# ocmod_module_playground_smt_v1.net
KiCad netlist of a schematic drawn in EAGLE
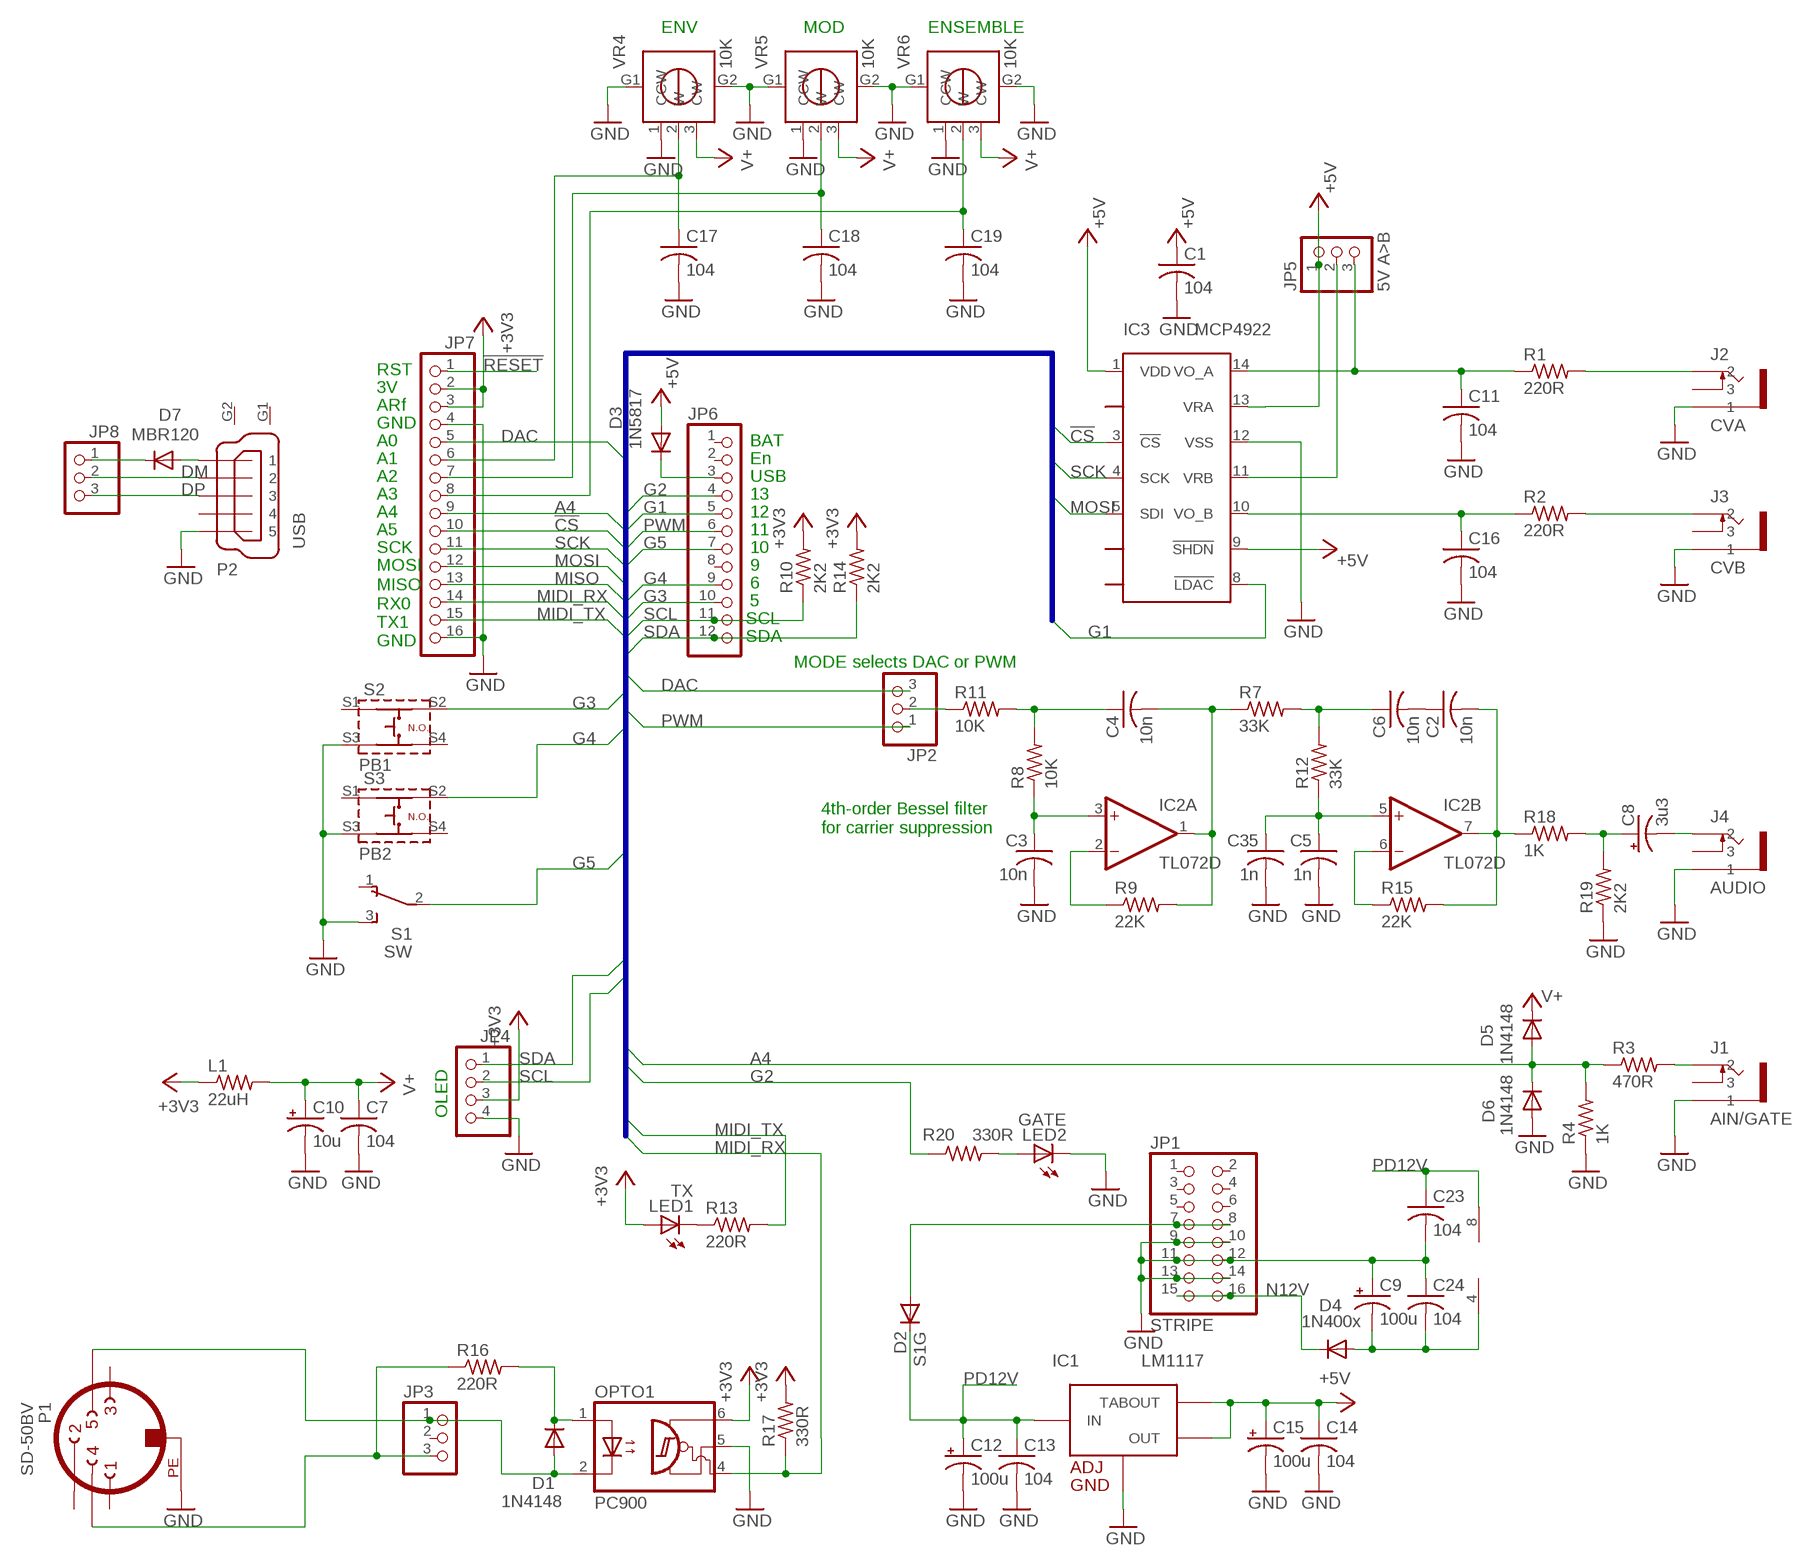
[diagram p0: schematic, sheet 1]

(export (version "E")
  (design (tool "Eeschema 10.0.6"))
  (components
    (comp (ref "C1")
      (value "104")
      (footprint "eagle-import:C0805K")
      (libsource (lib "eagle-import") (part "C-USC0805K"))
    )
    (comp (ref "C2")
      (value "10n")
      (footprint "eagle-import:C0805K")
      (libsource (lib "eagle-import") (part "C-USC0805K"))
    )
    (comp (ref "C3")
      (value "10n")
      (footprint "eagle-import:C0805K")
      (libsource (lib "eagle-import") (part "C-USC0805K"))
    )
    (comp (ref "C4")
      (value "10n")
      (footprint "eagle-import:C0805K")
      (libsource (lib "eagle-import") (part "C-USC0805K"))
    )
    (comp (ref "C5")
      (value "1n")
      (footprint "eagle-import:C0805K")
      (libsource (lib "eagle-import") (part "C-USC0805K"))
    )
    (comp (ref "C6")
      (value "10n")
      (footprint "eagle-import:C0805K")
      (libsource (lib "eagle-import") (part "C-USC0805K"))
    )
    (comp (ref "C7")
      (value "104")
      (footprint "eagle-import:C0805K")
      (libsource (lib "eagle-import") (part "C-USC0805K"))
    )
    (comp (ref "C8")
      (value "3u3")
      (footprint "eagle-import:B_3528-21R")
      (libsource (lib "eagle-import") (part "CPOL-USB/3528-21R"))
    )
    (comp (ref "C9")
      (value "100u")
      (footprint "eagle-import:B_3528-21R")
      (libsource (lib "eagle-import") (part "CPOL-USB/3528-21R"))
    )
    (comp (ref "C10")
      (value "10u")
      (footprint "eagle-import:B_3528-21R")
      (libsource (lib "eagle-import") (part "CPOL-USB/3528-21R"))
    )
    (comp (ref "C11")
      (value "104")
      (footprint "eagle-import:C0805K")
      (libsource (lib "eagle-import") (part "C-USC0805K"))
    )
    (comp (ref "C12")
      (value "100u")
      (footprint "eagle-import:B_3528-21R")
      (libsource (lib "eagle-import") (part "CPOL-USB/3528-21R"))
    )
    (comp (ref "C13")
      (value "104")
      (footprint "eagle-import:C0805K")
      (libsource (lib "eagle-import") (part "C-USC0805K"))
    )
    (comp (ref "C14")
      (value "104")
      (footprint "eagle-import:C0805K")
      (libsource (lib "eagle-import") (part "C-USC0805K"))
    )
    (comp (ref "C15")
      (value "100u")
      (footprint "eagle-import:B_3528-21R")
      (libsource (lib "eagle-import") (part "CPOL-USB/3528-21R"))
    )
    (comp (ref "C16")
      (value "104")
      (footprint "eagle-import:C0805K")
      (libsource (lib "eagle-import") (part "C-USC0805K"))
    )
    (comp (ref "C17")
      (value "104")
      (footprint "eagle-import:C0805K")
      (libsource (lib "eagle-import") (part "C-USC0805K"))
    )
    (comp (ref "C18")
      (value "104")
      (footprint "eagle-import:C0805K")
      (libsource (lib "eagle-import") (part "C-USC0805K"))
    )
    (comp (ref "C19")
      (value "104")
      (footprint "eagle-import:C0805K")
      (libsource (lib "eagle-import") (part "C-USC0805K"))
    )
    (comp (ref "C23")
      (value "104")
      (footprint "eagle-import:C0805K")
      (libsource (lib "eagle-import") (part "C-USC0805K"))
    )
    (comp (ref "C24")
      (value "104")
      (footprint "eagle-import:C0805K")
      (libsource (lib "eagle-import") (part "C-USC0805K"))
    )
    (comp (ref "C35")
      (value "1n")
      (footprint "eagle-import:C0805K")
      (libsource (lib "eagle-import") (part "C-USC0805K"))
    )
    (comp (ref "D1")
      (value "1N4148")
      (footprint "eagle-import:SOD123")
      (libsource (lib "eagle-import") (part "DIODE-SOD123"))
    )
    (comp (ref "D2")
      (value "S1G")
      (footprint "eagle-import:DO-214AC")
      (libsource (lib "eagle-import") (part "DIODE-DO-214AC"))
    )
    (comp (ref "D3")
      (value "1N5817")
      (footprint "eagle-import:DO214AC")
      (libsource (lib "eagle-import") (part "DIODE-DO214AC"))
    )
    (comp (ref "D4")
      (value "1N400x")
      (footprint "eagle-import:DO-214AC")
      (libsource (lib "eagle-import") (part "DIODE-DO-214AC"))
    )
    (comp (ref "D5")
      (value "1N4148")
      (footprint "eagle-import:SOD123")
      (libsource (lib "eagle-import") (part "DIODE-SOD123"))
    )
    (comp (ref "D6")
      (value "1N4148")
      (footprint "eagle-import:SOD123")
      (libsource (lib "eagle-import") (part "DIODE-SOD123"))
    )
    (comp (ref "D7")
      (value "MBR120")
      (footprint "eagle-import:SOD123")
      (libsource (lib "eagle-import") (part "DIODE-SOD123"))
    )
    (comp (ref "IC1")
      (value "LM1117")
      (footprint "eagle-import:SOT223")
      (libsource (lib "eagle-import") (part "LM1117"))
    )
    (comp (ref "IC2")
      (value "TL072D")
      (footprint "eagle-import:SO08")
      (libsource (lib "eagle-import") (part "TL072D"))
    )
    (comp (ref "IC3")
      (value "MCP4922")
      (footprint "eagle-import:SO14")
      (libsource (lib "eagle-import") (part "MCP4922D"))
    )
    (comp (ref "J1")
      (value "AIN/GATE")
      (footprint "eagle-import:WQP-PJ301M-12_JACK")
      (libsource (lib "eagle-import") (part "WQP-PJ301M-12_JACK"))
    )
    (comp (ref "J2")
      (value "CVA")
      (footprint "eagle-import:WQP-PJ301M-12_JACK")
      (libsource (lib "eagle-import") (part "WQP-PJ301M-12_JACK"))
    )
    (comp (ref "J3")
      (value "CVB")
      (footprint "eagle-import:WQP-PJ301M-12_JACK")
      (libsource (lib "eagle-import") (part "WQP-PJ301M-12_JACK"))
    )
    (comp (ref "J4")
      (value "AUDIO")
      (footprint "eagle-import:WQP-PJ301M-12_JACK")
      (libsource (lib "eagle-import") (part "WQP-PJ301M-12_JACK"))
    )
    (comp (ref "JP1")
      (value "STRIPE")
      (footprint "eagle-import:2X08")
      (libsource (lib "eagle-import") (part "PINHD-2X8"))
    )
    (comp (ref "JP2")
      (value "PINHD-1X3")
      (footprint "eagle-import:1X03")
      (libsource (lib "eagle-import") (part "PINHD-1X3"))
    )
    (comp (ref "JP3")
      (value "PINHD-1X3")
      (footprint "eagle-import:1X03")
      (libsource (lib "eagle-import") (part "pinhead_PINHD-1X3"))
    )
    (comp (ref "JP4")
      (value "PINHD-1X4")
      (footprint "eagle-import:1X04")
      (libsource (lib "eagle-import") (part "PINHD-1X4"))
    )
    (comp (ref "JP5")
      (value "5V A>B")
      (footprint "eagle-import:1X03")
      (libsource (lib "eagle-import") (part "PINHD-1X3"))
    )
    (comp (ref "JP6")
      (value "PINHD-1X12")
      (footprint "eagle-import:1X12")
      (libsource (lib "eagle-import") (part "PINHD-1X12"))
    )
    (comp (ref "JP7")
      (value "PINHD-1X16")
      (footprint "eagle-import:1X16")
      (libsource (lib "eagle-import") (part "PINHD-1X16"))
    )
    (comp (ref "JP8")
      (value "PINHD-1X3")
      (footprint "eagle-import:1X03")
      (libsource (lib "eagle-import") (part "PINHD-1X3"))
    )
    (comp (ref "L1")
      (value "22uH")
      (footprint "eagle-import:R0805")
      (libsource (lib "eagle-import") (part "R-US_R0805"))
    )
    (comp (ref "LED1")
      (value "TX")
      (footprint "eagle-import:LED3MM")
      (libsource (lib "eagle-import") (part "LED3MM"))
    )
    (comp (ref "LED2")
      (value "GATE")
      (footprint "eagle-import:LED3MM")
      (libsource (lib "eagle-import") (part "LED3MM"))
    )
    (comp (ref "OPTO1")
      (value "PC900")
      (footprint "eagle-import:DIL06N")
      (libsource (lib "eagle-import") (part "H11L1-MN"))
    )
    (comp (ref "P1")
      (value "SD-50BV")
      (footprint "eagle-import:SD-50BV_P")
      (libsource (lib "eagle-import") (part "SD-50BV"))
    )
    (comp (ref "P2")
      (value "USB")
      (footprint "eagle-import:MINI_USB5_WURTH")
      (libsource (lib "eagle-import") (part "MINI_USB5_WURTH"))
    )
    (comp (ref "R1")
      (value "220R")
      (footprint "eagle-import:R0805")
      (libsource (lib "eagle-import") (part "R-US_R0805"))
    )
    (comp (ref "R2")
      (value "220R")
      (footprint "eagle-import:R0805")
      (libsource (lib "eagle-import") (part "R-US_R0805"))
    )
    (comp (ref "R3")
      (value "470R")
      (footprint "eagle-import:R0805")
      (libsource (lib "eagle-import") (part "R-US_R0805"))
    )
    (comp (ref "R4")
      (value "1K")
      (footprint "eagle-import:R0805")
      (libsource (lib "eagle-import") (part "R-US_R0805"))
    )
    (comp (ref "R7")
      (value "33K")
      (footprint "eagle-import:R0805")
      (libsource (lib "eagle-import") (part "R-US_R0805"))
    )
    (comp (ref "R8")
      (value "10K")
      (footprint "eagle-import:R0805")
      (libsource (lib "eagle-import") (part "R-US_R0805"))
    )
    (comp (ref "R9")
      (value "22K")
      (footprint "eagle-import:R0805")
      (libsource (lib "eagle-import") (part "R-US_R0805"))
    )
    (comp (ref "R10")
      (value "2K2")
      (footprint "eagle-import:R0805")
      (libsource (lib "eagle-import") (part "R-US_R0805"))
    )
    (comp (ref "R11")
      (value "10K")
      (footprint "eagle-import:R0805")
      (libsource (lib "eagle-import") (part "R-US_R0805"))
    )
    (comp (ref "R12")
      (value "33K")
      (footprint "eagle-import:R0805")
      (libsource (lib "eagle-import") (part "R-US_R0805"))
    )
    (comp (ref "R13")
      (value "220R")
      (footprint "eagle-import:R0805")
      (libsource (lib "eagle-import") (part "R-US_R0805"))
    )
    (comp (ref "R14")
      (value "2K2")
      (footprint "eagle-import:R0805")
      (libsource (lib "eagle-import") (part "R-US_R0805"))
    )
    (comp (ref "R15")
      (value "22K")
      (footprint "eagle-import:R0805")
      (libsource (lib "eagle-import") (part "R-US_R0805"))
    )
    (comp (ref "R16")
      (value "220R")
      (footprint "eagle-import:R0805")
      (libsource (lib "eagle-import") (part "R-US_R0805"))
    )
    (comp (ref "R17")
      (value "330R")
      (footprint "eagle-import:R0805")
      (libsource (lib "eagle-import") (part "R-US_R0805"))
    )
    (comp (ref "R18")
      (value "1K")
      (footprint "eagle-import:R0805")
      (libsource (lib "eagle-import") (part "R-US_R0805"))
    )
    (comp (ref "R19")
      (value "2K2")
      (footprint "eagle-import:R0805")
      (libsource (lib "eagle-import") (part "R-US_R0805"))
    )
    (comp (ref "R20")
      (value "330R")
      (footprint "eagle-import:R0805")
      (libsource (lib "eagle-import") (part "R-US_R0805"))
    )
    (comp (ref "S1")
      (value "SW")
      (footprint "eagle-import:TL3XPO")
      (libsource (lib "eagle-import") (part "TL36PO"))
    )
    (comp (ref "S2")
      (value "PB1")
      (footprint "eagle-import:TACTSW_6MM_P")
      (libsource (lib "eagle-import") (part "TACTSW_6MM"))
    )
    (comp (ref "S3")
      (value "PB2")
      (footprint "eagle-import:TACTSW_6MM_P")
      (libsource (lib "eagle-import") (part "TACTSW_6MM"))
    )
    (comp (ref "VR4")
      (value "10K")
      (footprint "eagle-import:ALPHA_9MM_VERT_P")
      (libsource (lib "eagle-import") (part "ALPHA_9MM_VERT"))
    )
    (comp (ref "VR5")
      (value "10K")
      (footprint "eagle-import:ALPHA_9MM_VERT_P")
      (libsource (lib "eagle-import") (part "ALPHA_9MM_VERT"))
    )
    (comp (ref "VR6")
      (value "10K")
      (footprint "eagle-import:ALPHA_9MM_VERT_P")
      (libsource (lib "eagle-import") (part "ALPHA_9MM_VERT"))
    )
  )
  (nets
    (net (code "1") (name "+3V3") (class "Default")
      (node (ref "JP4") (pin "3") (pinfunction "3_3") (pintype "passive"))
      (node (ref "JP7") (pin "2") (pinfunction "2_2") (pintype "passive"))
      (node (ref "JP7") (pin "3") (pinfunction "3_3") (pintype "passive"))
      (node (ref "L1") (pin "1") (pinfunction "1_1") (pintype "passive"))
      (node (ref "LED1") (pin "A") (pinfunction "A_A") (pintype "passive"))
      (node (ref "OPTO1") (pin "6") (pinfunction "VCC_6") (pintype "passive"))
      (node (ref "R10") (pin "2") (pinfunction "2_2") (pintype "passive"))
      (node (ref "R14") (pin "2") (pinfunction "2_2") (pintype "passive"))
      (node (ref "R17") (pin "2") (pinfunction "2_2") (pintype "passive"))
    )
    (net (code "2") (name "+5V") (class "Default")
      (node (ref "C1") (pin "1") (pinfunction "1_1") (pintype "passive"))
      (node (ref "C14") (pin "1") (pinfunction "1_1") (pintype "passive"))
      (node (ref "C15") (pin "+") (pinfunction "+_+") (pintype "passive"))
      (node (ref "D3") (pin "A") (pinfunction "A_A") (pintype "passive"))
      (node (ref "IC1") (pin "1") (pinfunction "TABOUT_1") (pintype "passive"))
      (node (ref "IC1") (pin "4") (pinfunction "OUT_4") (pintype "passive"))
      (node (ref "IC3") (pin "1") (pinfunction "VDD_1") (pintype "bidirectional"))
      (node (ref "IC3") (pin "13") (pinfunction "VRA_13") (pintype "bidirectional"))
      (node (ref "IC3") (pin "9") (pinfunction "~{SHDN}_9") (pintype "bidirectional"))
      (node (ref "JP5") (pin "1") (pinfunction "1_1") (pintype "passive"))
    )
    (net (code "3") (name "/A4") (class "Default")
      (node (ref "D5") (pin "A") (pinfunction "A_A") (pintype "passive"))
      (node (ref "D6") (pin "C") (pinfunction "C_C") (pintype "passive"))
      (node (ref "JP7") (pin "9") (pinfunction "9_9") (pintype "passive"))
      (node (ref "R3") (pin "1") (pinfunction "1_1") (pintype "passive"))
      (node (ref "R4") (pin "2") (pinfunction "2_2") (pintype "passive"))
    )
    (net (code "4") (name "/DAC") (class "Default")
      (node (ref "JP2") (pin "3") (pinfunction "3_3") (pintype "passive"))
      (node (ref "JP7") (pin "5") (pinfunction "5_5") (pintype "passive"))
    )
    (net (code "5") (name "/DM") (class "Default")
      (node (ref "JP8") (pin "2") (pinfunction "2_2") (pintype "passive"))
      (node (ref "P2") (pin "2") (pinfunction "2_2") (pintype "passive"))
    )
    (net (code "6") (name "/DP") (class "Default")
      (node (ref "JP8") (pin "3") (pinfunction "3_3") (pintype "passive"))
      (node (ref "P2") (pin "3") (pinfunction "3_3") (pintype "passive"))
    )
    (net (code "7") (name "/G1") (class "Default")
      (node (ref "IC3") (pin "8") (pinfunction "~{LDAC}_8") (pintype "bidirectional"))
      (node (ref "JP6") (pin "5") (pinfunction "5_5") (pintype "passive"))
    )
    (net (code "8") (name "/G2") (class "Default")
      (node (ref "JP6") (pin "4") (pinfunction "4_4") (pintype "passive"))
      (node (ref "R20") (pin "1") (pinfunction "1_1") (pintype "passive"))
    )
    (net (code "9") (name "/G3") (class "Default")
      (node (ref "JP6") (pin "10") (pinfunction "10_10") (pintype "passive"))
      (node (ref "S2") (pin "S2") (pinfunction "2_S2") (pintype "passive"))
    )
    (net (code "10") (name "/G4") (class "Default")
      (node (ref "JP6") (pin "9") (pinfunction "9_9") (pintype "passive"))
      (node (ref "S3") (pin "S2") (pinfunction "2_S2") (pintype "passive"))
    )
    (net (code "11") (name "/G5") (class "Default")
      (node (ref "JP6") (pin "7") (pinfunction "7_7") (pintype "passive"))
      (node (ref "S1") (pin "2") (pinfunction "P_2") (pintype "passive"))
    )
    (net (code "12") (name "/MIDI_RX") (class "Default")
      (node (ref "JP7") (pin "14") (pinfunction "14_14") (pintype "passive"))
      (node (ref "OPTO1") (pin "4") (pinfunction "VO_4") (pintype "passive"))
      (node (ref "R17") (pin "1") (pinfunction "1_1") (pintype "passive"))
    )
    (net (code "13") (name "/MIDI_TX") (class "Default")
      (node (ref "JP7") (pin "15") (pinfunction "15_15") (pintype "passive"))
      (node (ref "R13") (pin "2") (pinfunction "2_2") (pintype "passive"))
    )
    (net (code "14") (name "/MISO") (class "Default")
      (node (ref "JP7") (pin "13") (pinfunction "13_13") (pintype "passive"))
    )
    (net (code "15") (name "/MOSI") (class "Default")
      (node (ref "IC3") (pin "5") (pinfunction "SDI_5") (pintype "bidirectional"))
      (node (ref "JP7") (pin "12") (pinfunction "12_12") (pintype "passive"))
    )
    (net (code "16") (name "/N12V") (class "Default")
      (node (ref "D4") (pin "C") (pinfunction "C_C") (pintype "passive"))
      (node (ref "JP1") (pin "15") (pinfunction "15_15") (pintype "passive"))
      (node (ref "JP1") (pin "16") (pinfunction "16_16") (pintype "passive"))
    )
    (net (code "17") (name "/PD12V") (class "Default")
      (node (ref "C12") (pin "+") (pinfunction "+_+") (pintype "passive"))
      (node (ref "C13") (pin "1") (pinfunction "1_1") (pintype "passive"))
      (node (ref "C23") (pin "1") (pinfunction "1_1") (pintype "passive"))
      (node (ref "D2") (pin "C") (pinfunction "C_C") (pintype "passive"))
      (node (ref "IC1") (pin "3") (pinfunction "IN_3") (pintype "passive"))
      (node (ref "IC2") (pin "8") (pinfunction "V+_8") (pintype "power_in"))
    )
    (net (code "18") (name "/PWM") (class "Default")
      (node (ref "JP2") (pin "1") (pinfunction "1_1") (pintype "passive"))
      (node (ref "JP6") (pin "6") (pinfunction "6_6") (pintype "passive"))
    )
    (net (code "19") (name "/SCK") (class "Default")
      (node (ref "IC3") (pin "4") (pinfunction "SCK_4") (pintype "bidirectional"))
      (node (ref "JP7") (pin "11") (pinfunction "11_11") (pintype "passive"))
    )
    (net (code "20") (name "/SCL") (class "Default")
      (node (ref "JP4") (pin "2") (pinfunction "2_2") (pintype "passive"))
      (node (ref "JP6") (pin "11") (pinfunction "11_11") (pintype "passive"))
      (node (ref "R10") (pin "1") (pinfunction "1_1") (pintype "passive"))
    )
    (net (code "21") (name "/SDA") (class "Default")
      (node (ref "JP4") (pin "1") (pinfunction "1_1") (pintype "passive"))
      (node (ref "JP6") (pin "12") (pinfunction "12_12") (pintype "passive"))
      (node (ref "R14") (pin "1") (pinfunction "1_1") (pintype "passive"))
    )
    (net (code "22") (name "/~{CS}") (class "Default")
      (node (ref "IC3") (pin "3") (pinfunction "~{CS}_3") (pintype "bidirectional"))
      (node (ref "JP7") (pin "10") (pinfunction "10_10") (pintype "passive"))
    )
    (net (code "23") (name "/~{RESET}") (class "Default")
      (node (ref "JP7") (pin "1") (pinfunction "1_1") (pintype "passive"))
    )
    (net (code "24") (name "GND") (class "Default")
      (node (ref "C1") (pin "2") (pinfunction "2_2") (pintype "passive"))
      (node (ref "C10") (pin "-") (pinfunction "-_-") (pintype "passive"))
      (node (ref "C11") (pin "2") (pinfunction "2_2") (pintype "passive"))
      (node (ref "C12") (pin "-") (pinfunction "-_-") (pintype "passive"))
      (node (ref "C13") (pin "2") (pinfunction "2_2") (pintype "passive"))
      (node (ref "C14") (pin "2") (pinfunction "2_2") (pintype "passive"))
      (node (ref "C15") (pin "-") (pinfunction "-_-") (pintype "passive"))
      (node (ref "C16") (pin "2") (pinfunction "2_2") (pintype "passive"))
      (node (ref "C17") (pin "2") (pinfunction "2_2") (pintype "passive"))
      (node (ref "C18") (pin "2") (pinfunction "2_2") (pintype "passive"))
      (node (ref "C19") (pin "2") (pinfunction "2_2") (pintype "passive"))
      (node (ref "C23") (pin "2") (pinfunction "2_2") (pintype "passive"))
      (node (ref "C24") (pin "1") (pinfunction "1_1") (pintype "passive"))
      (node (ref "C3") (pin "2") (pinfunction "2_2") (pintype "passive"))
      (node (ref "C35") (pin "2") (pinfunction "2_2") (pintype "passive"))
      (node (ref "C5") (pin "2") (pinfunction "2_2") (pintype "passive"))
      (node (ref "C7") (pin "2") (pinfunction "2_2") (pintype "passive"))
      (node (ref "C9") (pin "+") (pinfunction "+_+") (pintype "passive"))
      (node (ref "D6") (pin "A") (pinfunction "A_A") (pintype "passive"))
      (node (ref "IC1") (pin "2") (pinfunction "ADJ/GND_2") (pintype "passive"))
      (node (ref "IC3") (pin "12") (pinfunction "VSS_12") (pintype "bidirectional"))
      (node (ref "J1") (pin "P$3") (pinfunction "1_P$3") (pintype "passive"))
      (node (ref "J2") (pin "P$3") (pinfunction "1_P$3") (pintype "passive"))
      (node (ref "J3") (pin "P$3") (pinfunction "1_P$3") (pintype "passive"))
      (node (ref "J4") (pin "P$3") (pinfunction "1_P$3") (pintype "passive"))
      (node (ref "JP1") (pin "10") (pinfunction "10_10") (pintype "passive"))
      (node (ref "JP1") (pin "11") (pinfunction "11_11") (pintype "passive"))
      (node (ref "JP1") (pin "12") (pinfunction "12_12") (pintype "passive"))
      (node (ref "JP1") (pin "13") (pinfunction "13_13") (pintype "passive"))
      (node (ref "JP1") (pin "14") (pinfunction "14_14") (pintype "passive"))
      (node (ref "JP1") (pin "9") (pinfunction "9_9") (pintype "passive"))
      (node (ref "JP4") (pin "4") (pinfunction "4_4") (pintype "passive"))
      (node (ref "JP7") (pin "16") (pinfunction "16_16") (pintype "passive"))
      (node (ref "JP7") (pin "4") (pinfunction "4_4") (pintype "passive"))
      (node (ref "LED2") (pin "K") (pinfunction "C_K") (pintype "passive"))
      (node (ref "OPTO1") (pin "5") (pinfunction "GND_5") (pintype "passive"))
      (node (ref "P1") (pin "PE") (pinfunction "PE_PE") (pintype "power_in"))
      (node (ref "P2") (pin "5") (pinfunction "5_5") (pintype "passive"))
      (node (ref "R19") (pin "1") (pinfunction "1_1") (pintype "passive"))
      (node (ref "R4") (pin "1") (pinfunction "1_1") (pintype "passive"))
      (node (ref "S1") (pin "3") (pinfunction "S_3") (pintype "passive"))
      (node (ref "S2") (pin "S3") (pinfunction "3_S3") (pintype "passive"))
      (node (ref "S3") (pin "S3") (pinfunction "3_S3") (pintype "passive"))
      (node (ref "VR4") (pin "1") (pinfunction "CCW_1") (pintype "bidirectional"))
      (node (ref "VR4") (pin "G1") (pinfunction "G1_G1") (pintype "bidirectional"))
      (node (ref "VR4") (pin "G2") (pinfunction "G2_G2") (pintype "bidirectional"))
      (node (ref "VR5") (pin "1") (pinfunction "CCW_1") (pintype "bidirectional"))
      (node (ref "VR5") (pin "G1") (pinfunction "G1_G1") (pintype "bidirectional"))
      (node (ref "VR5") (pin "G2") (pinfunction "G2_G2") (pintype "bidirectional"))
      (node (ref "VR6") (pin "1") (pinfunction "CCW_1") (pintype "bidirectional"))
      (node (ref "VR6") (pin "G1") (pinfunction "G1_G1") (pintype "bidirectional"))
      (node (ref "VR6") (pin "G2") (pinfunction "G2_G2") (pintype "bidirectional"))
    )
    (net (code "25") (name "Net-(C2-Pad1)") (class "Default")
      (node (ref "C2") (pin "1") (pinfunction "1_1") (pintype "passive"))
      (node (ref "C6") (pin "2") (pinfunction "2_2") (pintype "passive"))
    )
    (net (code "26") (name "Net-(C4-Pad1)") (class "Default")
      (node (ref "C4") (pin "1") (pinfunction "1_1") (pintype "passive"))
      (node (ref "R11") (pin "2") (pinfunction "2_2") (pintype "passive"))
      (node (ref "R8") (pin "2") (pinfunction "2_2") (pintype "passive"))
    )
    (net (code "27") (name "Net-(C6-Pad1)") (class "Default")
      (node (ref "C6") (pin "1") (pinfunction "1_1") (pintype "passive"))
      (node (ref "R12") (pin "2") (pinfunction "2_2") (pintype "passive"))
      (node (ref "R7") (pin "2") (pinfunction "2_2") (pintype "passive"))
    )
    (net (code "28") (name "Net-(C8-Pad+)") (class "Default")
      (node (ref "C8") (pin "+") (pinfunction "+_+") (pintype "passive"))
      (node (ref "R18") (pin "2") (pinfunction "2_2") (pintype "passive"))
      (node (ref "R19") (pin "2") (pinfunction "2_2") (pintype "passive"))
    )
    (net (code "29") (name "Net-(D2-PadA)") (class "Default")
      (node (ref "D2") (pin "A") (pinfunction "A_A") (pintype "passive"))
      (node (ref "JP1") (pin "7") (pinfunction "7_7") (pintype "passive"))
      (node (ref "JP1") (pin "8") (pinfunction "8_8") (pintype "passive"))
    )
    (net (code "30") (name "Net-(D3-PadC)") (class "Default")
      (node (ref "D3") (pin "C") (pinfunction "C_C") (pintype "passive"))
      (node (ref "JP6") (pin "3") (pinfunction "3_3") (pintype "passive"))
    )
    (net (code "31") (name "Net-(D7-PadA)") (class "Default")
      (node (ref "D7") (pin "A") (pinfunction "A_A") (pintype "passive"))
      (node (ref "P2") (pin "1") (pinfunction "1_1") (pintype "passive"))
    )
    (net (code "32") (name "Net-(D7-PadC)") (class "Default")
      (node (ref "D7") (pin "C") (pinfunction "C_C") (pintype "passive"))
      (node (ref "JP8") (pin "1") (pinfunction "1_1") (pintype "passive"))
    )
    (net (code "33") (name "Net-(IC2A-+IN)") (class "Default")
      (node (ref "C3") (pin "1") (pinfunction "1_1") (pintype "passive"))
      (node (ref "IC2") (pin "3") (pinfunction "+IN_3") (pintype "input"))
      (node (ref "R8") (pin "1") (pinfunction "1_1") (pintype "passive"))
    )
    (net (code "34") (name "Net-(IC2A--IN)") (class "Default")
      (node (ref "IC2") (pin "2") (pinfunction "-IN_2") (pintype "input"))
      (node (ref "R9") (pin "1") (pinfunction "1_1") (pintype "passive"))
    )
    (net (code "35") (name "Net-(IC2A-OUT)") (class "Default")
      (node (ref "C4") (pin "2") (pinfunction "2_2") (pintype "passive"))
      (node (ref "IC2") (pin "1") (pinfunction "OUT_1") (pintype "output"))
      (node (ref "R7") (pin "1") (pinfunction "1_1") (pintype "passive"))
      (node (ref "R9") (pin "2") (pinfunction "2_2") (pintype "passive"))
    )
    (net (code "36") (name "Net-(IC2B-+IN)") (class "Default")
      (node (ref "C35") (pin "1") (pinfunction "1_1") (pintype "passive"))
      (node (ref "C5") (pin "1") (pinfunction "1_1") (pintype "passive"))
      (node (ref "IC2") (pin "5") (pinfunction "+IN_5") (pintype "input"))
      (node (ref "R12") (pin "1") (pinfunction "1_1") (pintype "passive"))
    )
    (net (code "37") (name "Net-(IC2B--IN)") (class "Default")
      (node (ref "IC2") (pin "6") (pinfunction "-IN_6") (pintype "input"))
      (node (ref "R15") (pin "1") (pinfunction "1_1") (pintype "passive"))
    )
    (net (code "38") (name "Net-(IC2B-OUT)") (class "Default")
      (node (ref "C2") (pin "2") (pinfunction "2_2") (pintype "passive"))
      (node (ref "IC2") (pin "7") (pinfunction "OUT_7") (pintype "output"))
      (node (ref "R15") (pin "2") (pinfunction "2_2") (pintype "passive"))
      (node (ref "R18") (pin "1") (pinfunction "1_1") (pintype "passive"))
    )
    (net (code "39") (name "Net-(IC2C-V-)") (class "Default")
      (node (ref "C24") (pin "2") (pinfunction "2_2") (pintype "passive"))
      (node (ref "C9") (pin "-") (pinfunction "-_-") (pintype "passive"))
      (node (ref "D4") (pin "A") (pinfunction "A_A") (pintype "passive"))
      (node (ref "IC2") (pin "4") (pinfunction "V-_4") (pintype "power_in"))
    )
    (net (code "40") (name "Net-(IC3-VO_A)") (class "Default")
      (node (ref "C11") (pin "1") (pinfunction "1_1") (pintype "passive"))
      (node (ref "IC3") (pin "14") (pinfunction "VO_A_14") (pintype "bidirectional"))
      (node (ref "JP5") (pin "3") (pinfunction "3_3") (pintype "passive"))
      (node (ref "R1") (pin "1") (pinfunction "1_1") (pintype "passive"))
    )
    (net (code "41") (name "Net-(IC3-VO_B)") (class "Default")
      (node (ref "C16") (pin "1") (pinfunction "1_1") (pintype "passive"))
      (node (ref "IC3") (pin "10") (pinfunction "VO_B_10") (pintype "bidirectional"))
      (node (ref "R2") (pin "1") (pinfunction "1_1") (pintype "passive"))
    )
    (net (code "42") (name "Net-(IC3-VRB)") (class "Default")
      (node (ref "IC3") (pin "11") (pinfunction "VRB_11") (pintype "bidirectional"))
      (node (ref "JP5") (pin "2") (pinfunction "2_2") (pintype "passive"))
    )
    (net (code "43") (name "Net-(J1-2)") (class "Default")
      (node (ref "J1") (pin "P$1") (pinfunction "2_P$1") (pintype "passive"))
      (node (ref "R3") (pin "2") (pinfunction "2_2") (pintype "passive"))
    )
    (net (code "44") (name "Net-(J2-2)") (class "Default")
      (node (ref "J2") (pin "P$1") (pinfunction "2_P$1") (pintype "passive"))
      (node (ref "R1") (pin "2") (pinfunction "2_2") (pintype "passive"))
    )
    (net (code "45") (name "Net-(J3-2)") (class "Default")
      (node (ref "J3") (pin "P$1") (pinfunction "2_P$1") (pintype "passive"))
      (node (ref "R2") (pin "2") (pinfunction "2_2") (pintype "passive"))
    )
    (net (code "46") (name "Net-(J4-2)") (class "Default")
      (node (ref "C8") (pin "-") (pinfunction "-_-") (pintype "passive"))
      (node (ref "J4") (pin "P$1") (pinfunction "2_P$1") (pintype "passive"))
    )
    (net (code "47") (name "Net-(JP2-Pad2)") (class "Default")
      (node (ref "JP2") (pin "2") (pinfunction "2_2") (pintype "passive"))
      (node (ref "R11") (pin "1") (pinfunction "1_1") (pintype "passive"))
    )
    (net (code "48") (name "Net-(JP3-Pad3)") (class "Default")
      (node (ref "JP3") (pin "3") (pinfunction "3_3") (pintype "passive"))
      (node (ref "P1") (pin "4") (pinfunction "4_4") (pintype "passive"))
      (node (ref "R16") (pin "1") (pinfunction "1_1") (pintype "passive"))
    )
    (net (code "49") (name "Net-(LED1-C)") (class "Default")
      (node (ref "LED1") (pin "K") (pinfunction "C_K") (pintype "passive"))
      (node (ref "R13") (pin "1") (pinfunction "1_1") (pintype "passive"))
    )
    (net (code "50") (name "Net-(LED2-PadA)") (class "Default")
      (node (ref "LED2") (pin "A") (pinfunction "A_A") (pintype "passive"))
      (node (ref "R20") (pin "2") (pinfunction "2_2") (pintype "passive"))
    )
    (net (code "51") (name "Net-(OPTO1-A)") (class "Default")
      (node (ref "D1") (pin "C") (pinfunction "C_C") (pintype "passive"))
      (node (ref "OPTO1") (pin "1") (pinfunction "A_1") (pintype "passive"))
      (node (ref "R16") (pin "2") (pinfunction "2_2") (pintype "passive"))
    )
    (net (code "52") (name "Net-(OPTO1-C)") (class "Default")
      (node (ref "D1") (pin "A") (pinfunction "A_A") (pintype "passive"))
      (node (ref "JP3") (pin "1") (pinfunction "1_1") (pintype "passive"))
      (node (ref "OPTO1") (pin "2") (pinfunction "C_2") (pintype "passive"))
      (node (ref "P1") (pin "5") (pinfunction "5_5") (pintype "passive"))
    )
    (net (code "53") (name "Net-(VR4-W)") (class "Default")
      (node (ref "C17") (pin "1") (pinfunction "1_1") (pintype "passive"))
      (node (ref "JP7") (pin "6") (pinfunction "6_6") (pintype "passive"))
      (node (ref "VR4") (pin "2") (pinfunction "W_2") (pintype "bidirectional"))
    )
    (net (code "54") (name "Net-(VR5-W)") (class "Default")
      (node (ref "C18") (pin "1") (pinfunction "1_1") (pintype "passive"))
      (node (ref "JP7") (pin "7") (pinfunction "7_7") (pintype "passive"))
      (node (ref "VR5") (pin "2") (pinfunction "W_2") (pintype "bidirectional"))
    )
    (net (code "55") (name "Net-(VR6-W)") (class "Default")
      (node (ref "C19") (pin "1") (pinfunction "1_1") (pintype "passive"))
      (node (ref "JP7") (pin "8") (pinfunction "8_8") (pintype "passive"))
      (node (ref "VR6") (pin "2") (pinfunction "W_2") (pintype "bidirectional"))
    )
    (net (code "56") (name "V+") (class "Default")
      (node (ref "C10") (pin "+") (pinfunction "+_+") (pintype "passive"))
      (node (ref "C7") (pin "1") (pinfunction "1_1") (pintype "passive"))
      (node (ref "D5") (pin "C") (pinfunction "C_C") (pintype "passive"))
      (node (ref "L1") (pin "2") (pinfunction "2_2") (pintype "passive"))
      (node (ref "VR4") (pin "3") (pinfunction "CW_3") (pintype "bidirectional"))
      (node (ref "VR5") (pin "3") (pinfunction "CW_3") (pintype "bidirectional"))
      (node (ref "VR6") (pin "3") (pinfunction "CW_3") (pintype "bidirectional"))
    )
    (net (code "57") (name "unconnected-(J1-3-PadP$2)") (class "Default")
      (node (ref "J1") (pin "P$2") (pinfunction "3_P$2") (pintype "passive"))
    )
    (net (code "58") (name "unconnected-(J2-3-PadP$2)") (class "Default")
      (node (ref "J2") (pin "P$2") (pinfunction "3_P$2") (pintype "passive"))
    )
    (net (code "59") (name "unconnected-(J3-3-PadP$2)") (class "Default")
      (node (ref "J3") (pin "P$2") (pinfunction "3_P$2") (pintype "passive"))
    )
    (net (code "60") (name "unconnected-(J4-3-PadP$2)") (class "Default")
      (node (ref "J4") (pin "P$2") (pinfunction "3_P$2") (pintype "passive"))
    )
    (net (code "61") (name "unconnected-(JP1-Pad1)") (class "Default")
      (node (ref "JP1") (pin "1") (pinfunction "1_1") (pintype "passive"))
    )
    (net (code "62") (name "unconnected-(JP1-Pad2)") (class "Default")
      (node (ref "JP1") (pin "2") (pinfunction "2_2") (pintype "passive"))
    )
    (net (code "63") (name "unconnected-(JP1-Pad3)") (class "Default")
      (node (ref "JP1") (pin "3") (pinfunction "3_3") (pintype "passive"))
    )
    (net (code "64") (name "unconnected-(JP1-Pad4)") (class "Default")
      (node (ref "JP1") (pin "4") (pinfunction "4_4") (pintype "passive"))
    )
    (net (code "65") (name "unconnected-(JP1-Pad5)") (class "Default")
      (node (ref "JP1") (pin "5") (pinfunction "5_5") (pintype "passive"))
    )
    (net (code "66") (name "unconnected-(JP1-Pad6)") (class "Default")
      (node (ref "JP1") (pin "6") (pinfunction "6_6") (pintype "passive"))
    )
    (net (code "67") (name "unconnected-(JP3-Pad2)") (class "Default")
      (node (ref "JP3") (pin "2") (pinfunction "2_2") (pintype "passive"))
    )
    (net (code "68") (name "unconnected-(JP6-Pad1)") (class "Default")
      (node (ref "JP6") (pin "1") (pinfunction "1_1") (pintype "passive"))
    )
    (net (code "69") (name "unconnected-(JP6-Pad2)") (class "Default")
      (node (ref "JP6") (pin "2") (pinfunction "2_2") (pintype "passive"))
    )
    (net (code "70") (name "unconnected-(JP6-Pad8)") (class "Default")
      (node (ref "JP6") (pin "8") (pinfunction "8_8") (pintype "passive"))
    )
    (net (code "71") (name "unconnected-(P1-Pad1)") (class "Default")
      (node (ref "P1") (pin "1") (pinfunction "1_1") (pintype "passive"))
    )
    (net (code "72") (name "unconnected-(P1-Pad2)") (class "Default")
      (node (ref "P1") (pin "2") (pinfunction "2_2") (pintype "passive"))
    )
    (net (code "73") (name "unconnected-(P1-Pad3)") (class "Default")
      (node (ref "P1") (pin "3") (pinfunction "3_3") (pintype "passive"))
    )
    (net (code "74") (name "unconnected-(P2-Pad4)") (class "Default")
      (node (ref "P2") (pin "4") (pinfunction "4_4") (pintype "passive"))
    )
    (net (code "75") (name "unconnected-(P2-PadG1)") (class "Default")
      (node (ref "P2") (pin "G1") (pinfunction "G1_G1") (pintype "passive"))
    )
    (net (code "76") (name "unconnected-(P2-PadG2)") (class "Default")
      (node (ref "P2") (pin "G2") (pinfunction "G2_G2") (pintype "passive"))
    )
    (net (code "77") (name "unconnected-(S1-O-Pad1)") (class "Default")
      (node (ref "S1") (pin "1") (pinfunction "O_1") (pintype "passive"))
    )
    (net (code "78") (name "unconnected-(S2-1-PadS1)") (class "Default")
      (node (ref "S2") (pin "S1") (pinfunction "1_S1") (pintype "passive"))
    )
    (net (code "79") (name "unconnected-(S2-4-PadS4)") (class "Default")
      (node (ref "S2") (pin "S4") (pinfunction "4_S4") (pintype "passive"))
    )
    (net (code "80") (name "unconnected-(S3-1-PadS1)") (class "Default")
      (node (ref "S3") (pin "S1") (pinfunction "1_S1") (pintype "passive"))
    )
    (net (code "81") (name "unconnected-(S3-4-PadS4)") (class "Default")
      (node (ref "S3") (pin "S4") (pinfunction "4_S4") (pintype "passive"))
    )
  )
)
